# ETH-input.net
KiCad netlist of a schematic drawn in Altium Designer
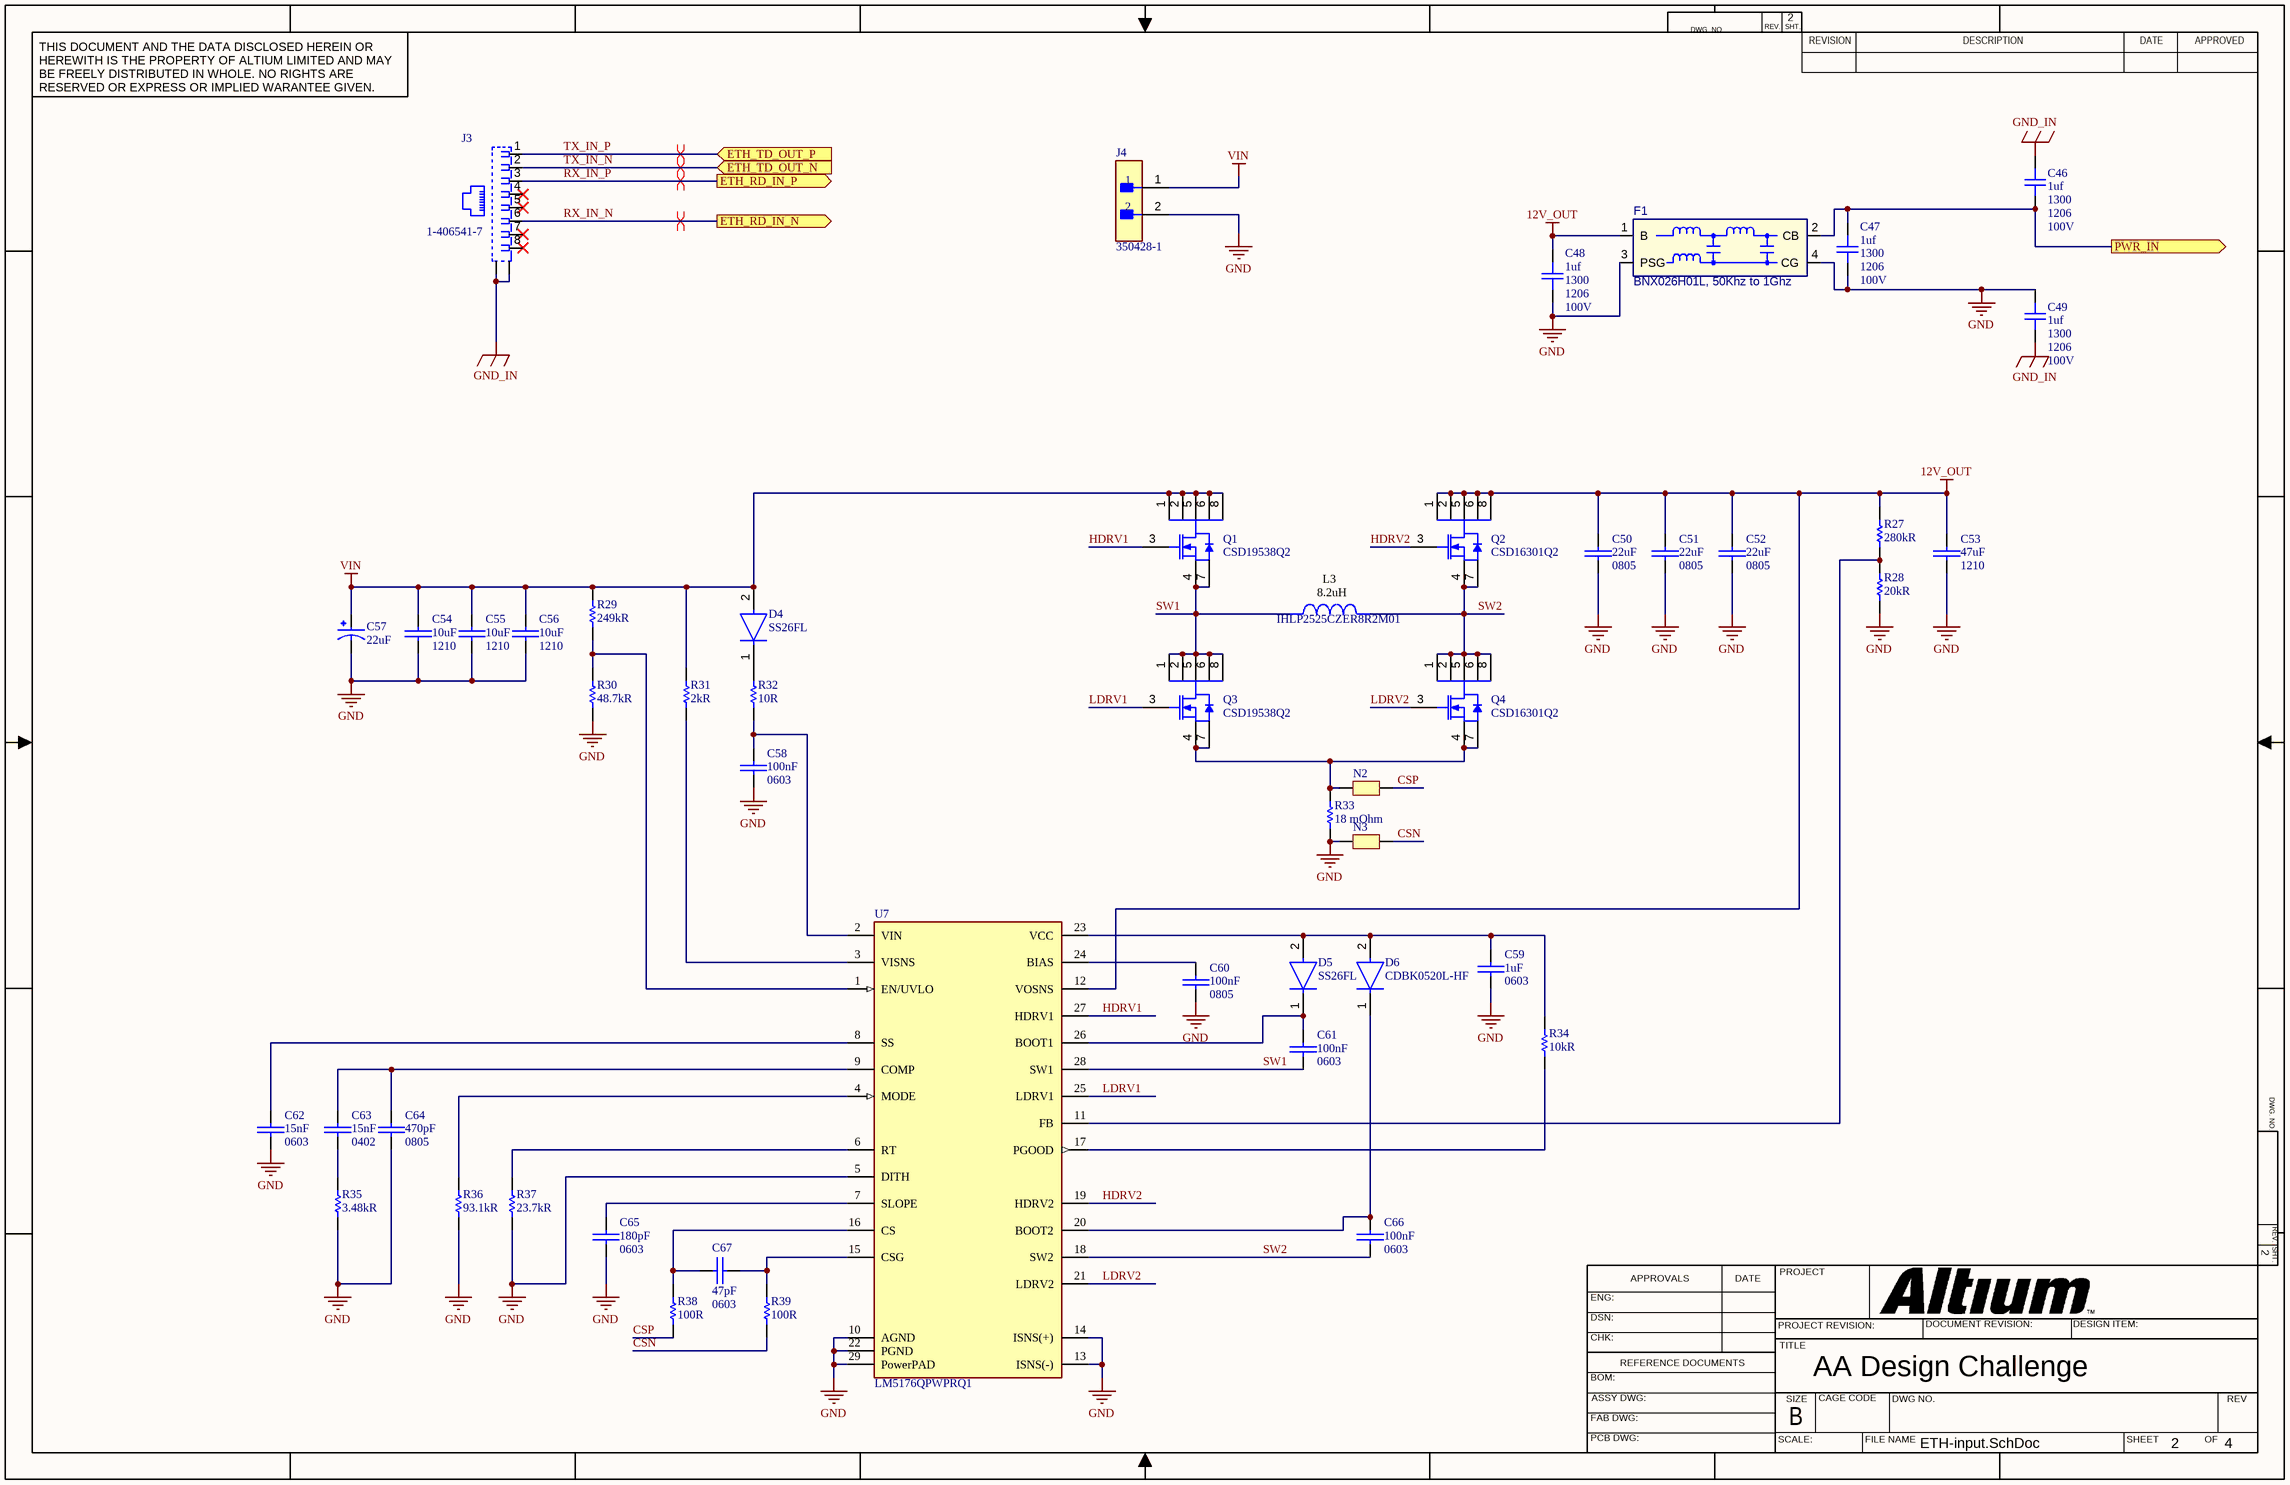
[diagram p0: ETH-input.SchDoc]

(export (version "E")
  (design (tool "Eeschema 10.0.6"))
  (components
    (comp (ref "C46")
      (value "1uf")
      (footprint "CAPC3216_IS1206N_3D")
      (description "Capacitor - 1uf 100V 10% X7R 1206")
      (fields
        (field (name "PACSTAR PN") "1300")
        (field (name "TOLERANCE") "+/-10%")
        (field (name "MANUFACTURER") "Samsung Electro-Mechanics")
        (field (name "CASE-EIA") "1206")
        (field (name "RATED VOLTAGE") "100V")
        (field (name "CHECKED BY") "xxx")
      )
      (libsource (lib "AA-Design-Challenge") (part "1300"))
    )
    (comp (ref "C47")
      (value "1uf")
      (footprint "CAPC3216_IS1206N_3D")
      (description "Capacitor - 1uf 100V 10% X7R 1206")
      (fields
        (field (name "PACSTAR PN") "1300")
        (field (name "TOLERANCE") "+/-10%")
        (field (name "MANUFACTURER") "Samsung Electro-Mechanics")
        (field (name "CASE-EIA") "1206")
        (field (name "RATED VOLTAGE") "100V")
        (field (name "CHECKED BY") "xxx")
      )
      (libsource (lib "AA-Design-Challenge") (part "1300"))
    )
    (comp (ref "C48")
      (value "1uf")
      (footprint "CAPC3216_IS1206N_3D")
      (description "Capacitor - 1uf 100V 10% X7R 1206")
      (fields
        (field (name "PACSTAR PN") "1300")
        (field (name "TOLERANCE") "+/-10%")
        (field (name "MANUFACTURER") "Samsung Electro-Mechanics")
        (field (name "CASE-EIA") "1206")
        (field (name "RATED VOLTAGE") "100V")
        (field (name "CHECKED BY") "xxx")
      )
      (libsource (lib "AA-Design-Challenge") (part "1300"))
    )
    (comp (ref "C49")
      (value "1uf")
      (footprint "CAPC3216_IS1206N_3D")
      (description "Capacitor - 1uf 100V 10% X7R 1206")
      (fields
        (field (name "PACSTAR PN") "1300")
        (field (name "TOLERANCE") "+/-10%")
        (field (name "MANUFACTURER") "Samsung Electro-Mechanics")
        (field (name "CASE-EIA") "1206")
        (field (name "RATED VOLTAGE") "100V")
        (field (name "CHECKED BY") "xxx")
      )
      (libsource (lib "AA-Design-Challenge") (part "1300"))
    )
    (comp (ref "C50")
      (value "22uF")
      (footprint "CAPC2012X145USR")
      (description "C Series 0805 22 uF 35 V ±20 % Tolerance X5R SMT Multilayer Ceramic Capacitor")
      (fields
        (field (name "MANUFACTURER") "TDK")
        (field (name "MANUFACTURER PART NUMBER") "C2012X5R1V226M125AC")
        (field (name "CASE/PACKAGE") "0805")
      )
      (libsource (lib "AA-Design-Challenge") (part "CAP CER 10UF 63V X7R 1210"))
    )
    (comp (ref "C51")
      (value "22uF")
      (footprint "CAPC2012X145USR")
      (description "C Series 0805 22 uF 35 V ±20 % Tolerance X5R SMT Multilayer Ceramic Capacitor")
      (fields
        (field (name "MANUFACTURER") "TDK")
        (field (name "MANUFACTURER PART NUMBER") "C2012X5R1V226M125AC")
        (field (name "CASE/PACKAGE") "0805")
      )
      (libsource (lib "AA-Design-Challenge") (part "CAP CER 10UF 63V X7R 1210"))
    )
    (comp (ref "C52")
      (value "22uF")
      (footprint "CAPC2012X145USR")
      (description "C Series 0805 22 uF 35 V ±20 % Tolerance X5R SMT Multilayer Ceramic Capacitor")
      (fields
        (field (name "MANUFACTURER") "TDK")
        (field (name "MANUFACTURER PART NUMBER") "C2012X5R1V226M125AC")
        (field (name "CASE/PACKAGE") "0805")
      )
      (libsource (lib "AA-Design-Challenge") (part "CAP CER 10UF 63V X7R 1210"))
    )
    (comp (ref "C53")
      (value "47uF")
      (footprint "C1210")
      (description "1210 47 uF 16 V ±10% Tolerance X5R SMT Multilayer Ceramic Capacitor")
      (fields
        (field (name "MANUFACTURER") "Samsung Electro-Mechanics")
        (field (name "MANUFACTURER PART NUMBER") "CL32A476KOJNNNE")
        (field (name "CASE/PACKAGE") "1210")
      )
      (libsource (lib "AA-Design-Challenge") (part "CAP CER 10UF 63V X7R 1210"))
    )
    (comp (ref "C54")
      (value "10uF")
      (footprint "AA-Design-Challenge:C1210")
      (description "Multilayer Ceramic Capacitors MLCC - SMD/SMT 1210 10uF 63volts *Derate Voltage/Temp")
      (fields
        (field (name "MANUFACTURER") "Samsung Electro-Mechanics")
        (field (name "MANUFACTURER PART NUMBER") "CL32B106KMVNNWE")
        (field (name "CASE/PACKAGE") "1210")
      )
      (libsource (lib "AA-Design-Challenge") (part "CAP CER 10UF 63V X7R 1210"))
    )
    (comp (ref "C55")
      (value "10uF")
      (footprint "AA-Design-Challenge:C1210")
      (description "Multilayer Ceramic Capacitors MLCC - SMD/SMT 1210 10uF 63volts *Derate Voltage/Temp")
      (fields
        (field (name "MANUFACTURER") "Samsung Electro-Mechanics")
        (field (name "MANUFACTURER PART NUMBER") "CL32B106KMVNNWE")
        (field (name "CASE/PACKAGE") "1210")
      )
      (libsource (lib "AA-Design-Challenge") (part "CAP CER 10UF 63V X7R 1210"))
    )
    (comp (ref "C56")
      (value "10uF")
      (footprint "AA-Design-Challenge:C1210")
      (description "Multilayer Ceramic Capacitors MLCC - SMD/SMT 1210 10uF 63volts *Derate Voltage/Temp")
      (fields
        (field (name "MANUFACTURER") "Samsung Electro-Mechanics")
        (field (name "MANUFACTURER PART NUMBER") "CL32B106KMVNNWE")
        (field (name "CASE/PACKAGE") "1210")
      )
      (libsource (lib "AA-Design-Challenge") (part "CAP CER 10UF 63V X7R 1210"))
    )
    (comp (ref "C57")
      (value "22uF")
      (footprint "CAP_EEEHC1H220XP")
      (description "22ÂµF 50V Aluminum Electrolytic Capacitors Radial, Can - SMD 3000 Hrs @ 105Â°C")
      (fields
        (field (name "MANUFACTURER") "Panasonic")
        (field (name "MANUFACTURER PART NUMBER") "EEEHC1H220XP")
      )
      (libsource (lib "AA-Design-Challenge") (part "EEEHC1H220XP"))
    )
    (comp (ref "C58")
      (value "100nF")
      (footprint "AA-Design-Challenge:CAP_0603")
      (description "CGA Series 0603 100 nF 50 V ±10 % Tolerance X7R SMT Multilayer Ceramic Capacitor")
      (fields
        (field (name "MANUFACTURER") "TDK")
        (field (name "MANUFACTURER PART NUMBER") "CGA3E2X7R1H104K080AA")
        (field (name "CASE/PACKAGE") "0603")
      )
      (libsource (lib "AA-Design-Challenge") (part "CAP CER 10UF 63V X7R 1210"))
    )
    (comp (ref "C59")
      (value "1uF")
      (footprint "AA-Design-Challenge:CAP_0603")
      (description "0603 1 uF 16 V ±10% Tolerance X7R SMT Multilayer Ceramic Capacitor")
      (fields
        (field (name "MANUFACTURER") "Samsung Electro-Mechanics")
        (field (name "MANUFACTURER PART NUMBER") "CL10B105KO8NNNC")
        (field (name "CASE/PACKAGE") "0603")
      )
      (libsource (lib "AA-Design-Challenge") (part "CAP CER 10UF 63V X7R 1210"))
    )
    (comp (ref "C60")
      (value "100nF")
      (footprint "AA-Design-Challenge:CAPC2012X145USR")
      (description "0805 100 nF 25V ±10 % Tolerance X7R Surface Mount Multilayer Ceramic Capacitor")
      (fields
        (field (name "MANUFACTURER") "Kyocera AVX")
        (field (name "MANUFACTURER PART NUMBER") "08053C104KAT2A")
        (field (name "CASE/PACKAGE") "0805")
      )
      (libsource (lib "AA-Design-Challenge") (part "CAP CER 10UF 63V X7R 1210"))
    )
    (comp (ref "C61")
      (value "100nF")
      (footprint "AA-Design-Challenge:CAP_0603")
      (description "Cap Ceramic 0.1uF 25V X7R 10% SMD 0603 125 Paper T/R")
      (fields
        (field (name "MANUFACTURER") "Kyocera AVX")
        (field (name "MANUFACTURER PART NUMBER") "06033C104KAT2A")
        (field (name "CASE/PACKAGE") "0603")
      )
      (libsource (lib "AA-Design-Challenge") (part "CAP CER 10UF 63V X7R 1210"))
    )
    (comp (ref "C62")
      (value "15nF")
      (footprint "AA-Design-Challenge:CAP_0603")
      (description "0603 C 15nF Ceramic Multilayer Capacitor; 25 V; +125degC; C0G Dielectric; +/-5%")
      (fields
        (field (name "MANUFACTURER") "KEMET")
        (field (name "MANUFACTURER PART NUMBER") "C0603C153J3GACTU")
        (field (name "CASE/PACKAGE") "0603")
      )
      (libsource (lib "AA-Design-Challenge") (part "CAP CER 10UF 63V X7R 1210"))
    )
    (comp (ref "C63")
      (value "15nF")
      (footprint "AA-Design-Challenge:CAPC1005X55USR")
      (description "Cap Ceramic 0.015uF 50V X7R 10% SMD 0402 125°C Punched Paper T/R")
      (fields
        (field (name "MANUFACTURER") "TDK")
        (field (name "MANUFACTURER PART NUMBER") "CGA2B3X7R1H153K050BB")
        (field (name "CASE/PACKAGE") "0402")
      )
      (libsource (lib "AA-Design-Challenge") (part "CAP CER 10UF 63V X7R 1210"))
    )
    (comp (ref "C64")
      (value "470pF")
      (footprint "AA-Design-Challenge:CAPC2012X145USR")
      (description "CAP CER 470PF 50V C0G/NP0 0805")
      (fields
        (field (name "MANUFACTURER") "Wurth Elektronik")
        (field (name "MANUFACTURER PART NUMBER") "885012007061")
        (field (name "CASE/PACKAGE") "0805")
      )
      (libsource (lib "AA-Design-Challenge") (part "CAP CER 10UF 63V X7R 1210"))
    )
    (comp (ref "C65")
      (value "180pF")
      (footprint "AA-Design-Challenge:CAP_0603")
      (description "Surface Mount Ceramic Multilayer Capacitor 180pF 5% C0G 50V 0603 Paper T/R")
      (fields
        (field (name "MANUFACTURER") "Yageo")
        (field (name "MANUFACTURER PART NUMBER") "CC0603JRNPO9BN181")
        (field (name "CASE/PACKAGE") "0603")
      )
      (libsource (lib "AA-Design-Challenge") (part "CAP CER 10UF 63V X7R 1210"))
    )
    (comp (ref "C66")
      (value "100nF")
      (footprint "AA-Design-Challenge:CAP_0603")
      (description "Cap Ceramic 0.1uF 25V X7R 10% SMD 0603 125 Paper T/R")
      (fields
        (field (name "MANUFACTURER") "Kyocera AVX")
        (field (name "MANUFACTURER PART NUMBER") "06033C104KAT2A")
        (field (name "CASE/PACKAGE") "0603")
      )
      (libsource (lib "AA-Design-Challenge") (part "CAP CER 10UF 63V X7R 1210"))
    )
    (comp (ref "C67")
      (value "47pF")
      (footprint "AA-Design-Challenge:CAP_0603")
      (description "0603 47 pF 50 V ±5% Tolerance C0G/NP0 Surface Mount Multilayer Ceramic Capacitor")
      (fields
        (field (name "MANUFACTURER") "Kyocera AVX")
        (field (name "MANUFACTURER PART NUMBER") "06035A470JAT2A")
        (field (name "CASE/PACKAGE") "0603")
      )
      (libsource (lib "AA-Design-Challenge") (part "CAP CER 10UF 63V X7R 1210"))
    )
    (comp (ref "D4")
      (value "SS26FL")
      (footprint "SOD-123F")
      (description "DIODE SCHOTTKY 60V 2A SOD123F")
      (fields (field (name "MANUFACTURER") "ON Semiconductor / Fairchild"))
      (libsource (lib "AA-Design-Challenge") (part "d7152d700b627762746794eb795d46e"))
    )
    (comp (ref "D5")
      (value "SS26FL")
      (footprint "SOD-123F")
      (description "DIODE SCHOTTKY 60V 2A SOD123F")
      (fields (field (name "MANUFACTURER") "ON Semiconductor / Fairchild"))
      (libsource (lib "AA-Design-Challenge") (part "d7152d700b627762746794eb795d46e"))
    )
    (comp (ref "D6")
      (value "CDBK0520L-HF")
      (footprint "AA-Design-Challenge:SOD-123F _CDBK")
      (description "DIODE SCHOTTKY 20V 500MA SOD123F")
      (fields
        (field (name "MANUFACTURER") "Nexperia")
        (field (name "MANUFACTURER PART NUMBER") "PMEG2005EH,115")
      )
      (libsource (lib "AA-Design-Challenge") (part "d7152d700b627762746794eb795d46e"))
    )
    (comp (ref "F1")
      (value "BNX026H01L, 50Khz to 1Ghz")
      (footprint "1359")
      (description "IC - FILTER, EMI 15A 50V 50KHZ-1GHZ SMD")
      (fields (field (name "MFG") "MURATA") (field (name "MANUFACTURER") "Murata"))
      (libsource (lib "AA-Design-Challenge") (part "1359"))
    )
    (comp (ref "J3")
      (value "1-406541-7")
      (footprint "TE_1-406507-5")
      (description "Conn RJ-45 F 8 POS 1.02mm Solder RA Thru-Hole 10 Terminal 1 Port Cat 5 Box/Tray")
      (fields (field (name "MANUFACTURER") "TE Connectivity"))
      (libsource (lib "AA-Design-Challenge") (part "1-406541-7"))
    )
    (comp (ref "J4")
      (value "350428-1")
      (footprint "FP-350428-1-MFG")
      (description "CONN HEADER VERT 2POS 6.35MM")
      (fields
        (field (name "OCTOPART") "https://octopart.com/350428-1-te+connectivity-46505355")
        (field (name "MANUFACTURER") "TE Connectivity")
      )
      (libsource (lib "AA-Design-Challenge") (part "3bc925449376181038e59eaffc5286c"))
    )
    (comp (ref "L3")
      (value "8.2uH")
      (footprint "INDM686X647X300N")
      (description "FIXED IND 8.2UH 4A 68 MOHM SMD")
      (fields
        (field (name "MANUFACTURER") "Vishay Dale")
        (field (name "MANUFACTURER PART NUMBER") "IHLP2525CZER8R2M01")
        (field (name "TOLERANCE") "20%")
      )
      (libsource (lib "AA-Design-Challenge") (part "L1"))
    )
    (comp (ref "N2")
      (value "NT")
      (footprint "Net Tie 10mil")
      (libsource (lib "OP_Library") (part "Net Tie 10mil"))
    )
    (comp (ref "N3")
      (value "NT")
      (footprint "Net Tie 10mil")
      (libsource (lib "OP_Library") (part "Net Tie 10mil"))
    )
    (comp (ref "Q1")
      (value "CSD19538Q2")
      (footprint "TRANS_6WSON_2X2")
      (description "100-V, N channel NexFET™ power MOSFET, single SON 2 mm x 2 mm, 59 mOhm 6-WSON -55 to 150")
      (fields
        (field (name "MANUFACTURER") "Texas Instruments")
        (field (name "MANUFACTURER PART NUMBER") "CSD19538Q2T")
      )
      (libsource (lib "AA-Design-Challenge") (part "CSD19538Q2"))
    )
    (comp (ref "Q2")
      (value "CSD16301Q2")
      (footprint "TRANS_6WSON_2X2")
      (description "MOSFET N-CH 25V 6-SON")
      (fields (field (name "MANUFACTURER") "Texas Instruments"))
      (libsource (lib "AA-Design-Challenge") (part "CSD16301Q2"))
    )
    (comp (ref "Q3")
      (value "CSD19538Q2")
      (footprint "TRANS_6WSON_2X2")
      (description "100-V, N channel NexFET™ power MOSFET, single SON 2 mm x 2 mm, 59 mOhm 6-WSON -55 to 150")
      (fields
        (field (name "MANUFACTURER") "Texas Instruments")
        (field (name "MANUFACTURER PART NUMBER") "CSD19538Q2T")
      )
      (libsource (lib "AA-Design-Challenge") (part "CSD19538Q2"))
    )
    (comp (ref "Q4")
      (value "CSD16301Q2")
      (footprint "TRANS_6WSON_2X2")
      (description "MOSFET N-CH 25V 6-SON")
      (fields (field (name "MANUFACTURER") "Texas Instruments"))
      (libsource (lib "AA-Design-Challenge") (part "CSD16301Q2"))
    )
    (comp (ref "R27")
      (value "280kR")
      (footprint "R0603")
      (description "Res Thick Film 0603 280K Ohm 1% 1/10W ±100ppm/°C Molded SMD SMD Paper T/R")
      (fields
        (field (name "MANUFACTURER") "Vishay")
        (field (name "MANUFACTURER PART NUMBER") "CRCW0603280KFKEA")
      )
      (libsource (lib "AA-Design-Challenge") (part "RES SMD 2K OHM 1% 1/10W 0603"))
    )
    (comp (ref "R28")
      (value "20kR")
      (footprint "R0603")
      (description "Res General Purpose Thick Film 0603 20K Ohm 1% 1/10W ±100ppm/°C Molded SMD Paper T/R")
      (fields
        (field (name "MANUFACTURER") "Yageo")
        (field (name "MANUFACTURER PART NUMBER") "RC0603FR-0720KL")
      )
      (libsource (lib "AA-Design-Challenge") (part "RES SMD 2K OHM 1% 1/10W 0603"))
    )
    (comp (ref "R29")
      (value "249kR")
      (footprint "RESC0603X26N")
      (description "Res Thick Film 0201 249K Ohm 1% 1/20W ±200ppm/°C Molded SMD Paper T/R")
      (fields
        (field (name "MANUFACTURER") "Yageo")
        (field (name "MANUFACTURER PART NUMBER") "RC0201FR-07249KL")
      )
      (libsource (lib "AA-Design-Challenge") (part "RES 249K OHM 1% 1/20W 0201"))
    )
    (comp (ref "R30")
      (value "48.7kR")
      (footprint "RESC1005X40USR")
      (description "Res Thick Film 0402 48.7K Ohm 1% 1/16W ±100ppm/°C Molded SMD SMD Paper T/R")
      (fields
        (field (name "MANUFACTURER") "Vishay")
        (field (name "MANUFACTURER PART NUMBER") "CRCW040248K7FKED")
      )
      (libsource (lib "AA-Design-Challenge") (part "RES SMD 48.7K OHM 1% 1/16W 0402"))
    )
    (comp (ref "R31")
      (value "2kR")
      (footprint "R0603")
      (description "Res Thick Film 0603 2K Ohm 1% 1/10W ±100ppm/°C Molded SMD Paper T/R")
      (fields
        (field (name "MANUFACTURER") "Vishay")
        (field (name "MANUFACTURER PART NUMBER") "CRCW06032K00FKEB")
      )
      (libsource (lib "AA-Design-Challenge") (part "RES SMD 2K OHM 1% 1/10W 0603"))
    )
    (comp (ref "R32")
      (value "10R")
      (footprint "R0603")
      (description "Res Thick Film 0603 10 Ohm 1% 1/10W ±200ppm/°C Molded SMD Paper T/R")
      (fields
        (field (name "MANUFACTURER") "Yageo")
        (field (name "MANUFACTURER PART NUMBER") "RC0603FR-0710RL")
      )
      (libsource (lib "AA-Design-Challenge") (part "RES SMD 2K OHM 1% 1/10W 0603"))
    )
    (comp (ref "R33")
      (value "18 mOhm")
      (footprint "RES 1206N - 71")
      (description "Res Thick Film 1206 0.018 Ohm 1% 1W ±75ppm/C Pad SMD Automotive T/R")
      (fields
        (field (name "MANUFACTURER") "Panasonic")
        (field (name "MANUFACTURER PART NUMBER") "ERJ8CWFR018V")
      )
      (libsource (lib "AA-Design-Challenge") (part "ERJ8CWFR018V"))
    )
    (comp (ref "R34")
      (value "10kR")
      (footprint "R0603")
      (description "RES SMD 10K OHM 1% 1/10W 0603")
      (fields
        (field (name "MANUFACTURER") "Yageo")
        (field (name "MANUFACTURER PART NUMBER") "RC0603FR-0710KL")
      )
      (libsource (lib "AA-Design-Challenge") (part "RES SMD 2K OHM 1% 1/10W 0603"))
    )
    (comp (ref "R35")
      (value "3.48kR")
      (footprint "AA-Design-Challenge:RESC1005X40USR")
      (description "Res Thick Film 0402 3.48K Ohm 1% 1/16W ±100ppm/°C Molded SMD Paper T/R")
      (fields
        (field (name "MANUFACTURER") "Vishay")
        (field (name "MANUFACTURER PART NUMBER") "CRCW04023K48FKED")
      )
      (libsource (lib "AA-Design-Challenge") (part "RES SMD 2K OHM 1% 1/10W 0603"))
    )
    (comp (ref "R36")
      (value "93.1kR")
      (footprint "AA-Design-Challenge:R0603")
      (description "Res Thick Film 0603 93.1K Ohm 1% 1/10W ±100ppm/°C Molded SMD SMD Paper T/R")
      (fields
        (field (name "MANUFACTURER") "Yageo")
        (field (name "MANUFACTURER PART NUMBER") "RC0603FR-0793K1L")
      )
      (libsource (lib "AA-Design-Challenge") (part "RES SMD 2K OHM 1% 1/10W 0603"))
    )
    (comp (ref "R37")
      (value "23.7kR")
      (footprint "RESC0603X26N")
      (description "Res General Purpose Thick Film 0201 23.7k Ohm 1% 1/20W ±200ppm/°C Molded SMD Paper T/R")
      (fields
        (field (name "MANUFACTURER") "Yageo")
        (field (name "MANUFACTURER PART NUMBER") "RC0201FR-0723K7L")
      )
      (libsource (lib "AA-Design-Challenge") (part "RES SMD 2K OHM 1% 1/10W 0603"))
    )
    (comp (ref "R38")
      (value "100R")
      (footprint "AA-Design-Challenge:R0603")
      (description "Res Thick Film 0603 100 Ohm 1% 1/10W ±100ppm/°C Molded SMD Paper T/R")
      (fields
        (field (name "MANUFACTURER") "Vishay Dale")
        (field (name "MANUFACTURER PART NUMBER") "CRCW0603100RFKEA")
      )
      (libsource (lib "AA-Design-Challenge") (part "RES SMD 2K OHM 1% 1/10W 0603"))
    )
    (comp (ref "R39")
      (value "100R")
      (footprint "R0603")
      (description "Res Thick Film 0603 100 Ohm 1% 1/10W ±100ppm/°C Molded SMD Paper T/R")
      (fields
        (field (name "MANUFACTURER") "Vishay Dale")
        (field (name "MANUFACTURER PART NUMBER") "CRCW0603100RFKEA")
      )
      (libsource (lib "AA-Design-Challenge") (part "RES SMD 2K OHM 1% 1/10W 0603"))
    )
    (comp (ref "U7")
      (value "LM5176QPWPRQ1")
      (footprint "IC_LM5176QPWPRQ1")
      (description "55-V wide VIN synchronous 4-switch buck-boost controller, AEC-Q100 qualified 28-HTSSOP -40 to 125")
      (fields (field (name "MANUFACTURER") "Texas Instruments"))
      (libsource (lib "AA-Design-Challenge") (part "LM5176QPWPRQ1"))
    )
  )
  (nets
    (net (code "1") (name "/CSN") (class "Default")
      (node (ref "N3") (pin "2") (pinfunction "2_2") (pintype "passive"))
      (node (ref "R39") (pin "1") (pinfunction "1_1") (pintype "passive"))
    )
    (net (code "2") (name "/CSP") (class "Default")
      (node (ref "N2") (pin "2") (pinfunction "2_2") (pintype "passive"))
      (node (ref "R38") (pin "1") (pinfunction "1_1") (pintype "passive"))
    )
    (net (code "3") (name "/HDRV1") (class "Default")
      (node (ref "Q1") (pin "3") (pinfunction "GATE_3") (pintype "passive"))
      (node (ref "U7") (pin "27") (pinfunction "HDRV1_27") (pintype "power_in"))
    )
    (net (code "4") (name "/HDRV2") (class "Default")
      (node (ref "Q2") (pin "3") (pinfunction "GATE_3") (pintype "passive"))
      (node (ref "U7") (pin "19") (pinfunction "HDRV2_19") (pintype "power_in"))
    )
    (net (code "5") (name "/LDRV1") (class "Default")
      (node (ref "Q3") (pin "3") (pinfunction "GATE_3") (pintype "passive"))
      (node (ref "U7") (pin "25") (pinfunction "LDRV1_25") (pintype "power_in"))
    )
    (net (code "6") (name "/LDRV2") (class "Default")
      (node (ref "Q4") (pin "3") (pinfunction "GATE_3") (pintype "passive"))
      (node (ref "U7") (pin "21") (pinfunction "LDRV2_21") (pintype "power_in"))
    )
    (net (code "7") (name "/PWR_IN") (class "Default")
      (node (ref "C46") (pin "2") (pinfunction "2_2") (pintype "passive"))
      (node (ref "C47") (pin "1") (pinfunction "1_1") (pintype "passive"))
      (node (ref "F1") (pin "2") (pinfunction "CB_2") (pintype "passive"))
    )
    (net (code "8") (name "/RX_IN_N") (class "Default")
      (node (ref "J3") (pin "6") (pinfunction "6_6") (pintype "passive"))
    )
    (net (code "9") (name "/RX_IN_P") (class "Default")
      (node (ref "J3") (pin "3") (pinfunction "3_3") (pintype "passive"))
    )
    (net (code "10") (name "/SW1") (class "Default")
      (node (ref "C61") (pin "2") (pinfunction "2_2") (pintype "passive"))
      (node (ref "L3") (pin "1") (pinfunction "1_1") (pintype "passive"))
      (node (ref "Q1") (pin "4") (pinfunction "SOURCE_4") (pintype "passive"))
      (node (ref "Q1") (pin "7") (pinfunction "SOURCE_7") (pintype "passive"))
      (node (ref "Q3") (pin "1") (pinfunction "DRAIN_1") (pintype "passive"))
      (node (ref "Q3") (pin "2") (pinfunction "DRAIN_2") (pintype "passive"))
      (node (ref "Q3") (pin "5") (pinfunction "DRAIN_5") (pintype "passive"))
      (node (ref "Q3") (pin "6") (pinfunction "DRAIN_6") (pintype "passive"))
      (node (ref "Q3") (pin "8") (pinfunction "DRAIN_8") (pintype "passive"))
      (node (ref "U7") (pin "28") (pinfunction "SW1_28") (pintype "power_in"))
    )
    (net (code "11") (name "/SW2") (class "Default")
      (node (ref "C66") (pin "2") (pinfunction "2_2") (pintype "passive"))
      (node (ref "L3") (pin "2") (pinfunction "2_2") (pintype "passive"))
      (node (ref "Q2") (pin "4") (pinfunction "SOURCE_4") (pintype "passive"))
      (node (ref "Q2") (pin "7") (pinfunction "SOURCE_7") (pintype "passive"))
      (node (ref "Q4") (pin "1") (pinfunction "DRAIN_1") (pintype "passive"))
      (node (ref "Q4") (pin "2") (pinfunction "DRAIN_2") (pintype "passive"))
      (node (ref "Q4") (pin "5") (pinfunction "DRAIN_5") (pintype "passive"))
      (node (ref "Q4") (pin "6") (pinfunction "DRAIN_6") (pintype "passive"))
      (node (ref "Q4") (pin "8") (pinfunction "DRAIN_8") (pintype "passive"))
      (node (ref "U7") (pin "18") (pinfunction "SW2_18") (pintype "power_in"))
    )
    (net (code "12") (name "/TX_IN_N") (class "Default")
      (node (ref "J3") (pin "2") (pinfunction "2_2") (pintype "passive"))
    )
    (net (code "13") (name "/TX_IN_P") (class "Default")
      (node (ref "J3") (pin "1") (pinfunction "1_1") (pintype "passive"))
    )
    (net (code "14") (name "12V_OUT") (class "Default")
      (node (ref "C48") (pin "1") (pinfunction "1_1") (pintype "passive"))
      (node (ref "C50") (pin "1") (pinfunction "1_1") (pintype "passive"))
      (node (ref "C51") (pin "1") (pinfunction "1_1") (pintype "passive"))
      (node (ref "C52") (pin "1") (pinfunction "1_1") (pintype "passive"))
      (node (ref "C53") (pin "1") (pinfunction "1_1") (pintype "passive"))
      (node (ref "F1") (pin "1") (pinfunction "B_1") (pintype "passive"))
      (node (ref "Q2") (pin "1") (pinfunction "DRAIN_1") (pintype "passive"))
      (node (ref "Q2") (pin "2") (pinfunction "DRAIN_2") (pintype "passive"))
      (node (ref "Q2") (pin "5") (pinfunction "DRAIN_5") (pintype "passive"))
      (node (ref "Q2") (pin "6") (pinfunction "DRAIN_6") (pintype "passive"))
      (node (ref "Q2") (pin "8") (pinfunction "DRAIN_8") (pintype "passive"))
      (node (ref "R27") (pin "2") (pinfunction "2_2") (pintype "passive"))
      (node (ref "U7") (pin "12") (pinfunction "VOSNS_12") (pintype "passive"))
    )
    (net (code "15") (name "GND") (class "Default")
      (node (ref "C47") (pin "2") (pinfunction "2_2") (pintype "passive"))
      (node (ref "C48") (pin "2") (pinfunction "2_2") (pintype "passive"))
      (node (ref "C49") (pin "2") (pinfunction "2_2") (pintype "passive"))
      (node (ref "C50") (pin "2") (pinfunction "2_2") (pintype "passive"))
      (node (ref "C51") (pin "2") (pinfunction "2_2") (pintype "passive"))
      (node (ref "C52") (pin "2") (pinfunction "2_2") (pintype "passive"))
      (node (ref "C53") (pin "2") (pinfunction "2_2") (pintype "passive"))
      (node (ref "C54") (pin "2") (pinfunction "2_2") (pintype "passive"))
      (node (ref "C55") (pin "2") (pinfunction "2_2") (pintype "passive"))
      (node (ref "C56") (pin "2") (pinfunction "2_2") (pintype "passive"))
      (node (ref "C57") (pin "2") (pinfunction "2_2") (pintype "passive"))
      (node (ref "C58") (pin "2") (pinfunction "2_2") (pintype "passive"))
      (node (ref "C59") (pin "2") (pinfunction "2_2") (pintype "passive"))
      (node (ref "C60") (pin "2") (pinfunction "2_2") (pintype "passive"))
      (node (ref "C62") (pin "2") (pinfunction "2_2") (pintype "passive"))
      (node (ref "C64") (pin "2") (pinfunction "2_2") (pintype "passive"))
      (node (ref "C65") (pin "2") (pinfunction "2_2") (pintype "passive"))
      (node (ref "F1") (pin "3") (pinfunction "PSG_3") (pintype "passive"))
      (node (ref "F1") (pin "4") (pinfunction "CG_4") (pintype "passive"))
      (node (ref "J4") (pin "2") (pinfunction "2_2") (pintype "passive"))
      (node (ref "N3") (pin "1") (pinfunction "1_1") (pintype "passive"))
      (node (ref "R28") (pin "1") (pinfunction "1_1") (pintype "passive"))
      (node (ref "R30") (pin "1") (pinfunction "1_1") (pintype "passive"))
      (node (ref "R33") (pin "1") (pinfunction "1_1") (pintype "passive"))
      (node (ref "R35") (pin "1") (pinfunction "1_1") (pintype "passive"))
      (node (ref "R36") (pin "1") (pinfunction "1_1") (pintype "passive"))
      (node (ref "R37") (pin "1") (pinfunction "1_1") (pintype "passive"))
      (node (ref "U7") (pin "10") (pinfunction "AGND_10") (pintype "power_in"))
      (node (ref "U7") (pin "13") (pinfunction "ISNS(-)_13") (pintype "passive"))
      (node (ref "U7") (pin "14") (pinfunction "ISNS(+)_14") (pintype "passive"))
      (node (ref "U7") (pin "22") (pinfunction "PGND_22") (pintype "power_in"))
      (node (ref "U7") (pin "29") (pinfunction "PowerPAD_29") (pintype "power_in"))
      (node (ref "U7") (pin "5") (pinfunction "DITH_5") (pintype "passive"))
    )
    (net (code "16") (name "GND_IN") (class "Default")
      (node (ref "C46") (pin "1") (pinfunction "1_1") (pintype "passive"))
      (node (ref "C49") (pin "1") (pinfunction "1_1") (pintype "passive"))
      (node (ref "J3") (pin "10") (pinfunction "S2_10") (pintype "passive"))
      (node (ref "J3") (pin "9") (pinfunction "S1_9") (pintype "passive"))
    )
    (net (code "17") (name "Net-(C63-Pad2)") (class "Default")
      (node (ref "C63") (pin "2") (pinfunction "2_2") (pintype "passive"))
      (node (ref "R35") (pin "2") (pinfunction "2_2") (pintype "passive"))
    )
    (net (code "18") (name "Net-(D4-C)") (class "Default")
      (node (ref "D4") (pin "1") (pinfunction "C_1") (pintype "passive"))
      (node (ref "R32") (pin "2") (pinfunction "2_2") (pintype "passive"))
    )
    (net (code "19") (name "Net-(D5-A)") (class "Default")
      (node (ref "C59") (pin "1") (pinfunction "1_1") (pintype "passive"))
      (node (ref "D5") (pin "2") (pinfunction "A_2") (pintype "passive"))
      (node (ref "D6") (pin "2") (pinfunction "A_2") (pintype "passive"))
      (node (ref "R34") (pin "2") (pinfunction "2_2") (pintype "passive"))
      (node (ref "U7") (pin "23") (pinfunction "VCC_23") (pintype "power_in"))
    )
    (net (code "20") (name "Net-(D5-C)") (class "Default")
      (node (ref "C61") (pin "1") (pinfunction "1_1") (pintype "passive"))
      (node (ref "D5") (pin "1") (pinfunction "C_1") (pintype "passive"))
      (node (ref "U7") (pin "26") (pinfunction "BOOT1_26") (pintype "power_in"))
    )
    (net (code "21") (name "Net-(D6-C)") (class "Default")
      (node (ref "C66") (pin "1") (pinfunction "1_1") (pintype "passive"))
      (node (ref "D6") (pin "1") (pinfunction "C_1") (pintype "passive"))
      (node (ref "U7") (pin "20") (pinfunction "BOOT2_20") (pintype "power_in"))
    )
    (net (code "22") (name "Net-(N2-Pad1)") (class "Default")
      (node (ref "N2") (pin "1") (pinfunction "1_1") (pintype "passive"))
      (node (ref "Q3") (pin "4") (pinfunction "SOURCE_4") (pintype "passive"))
      (node (ref "Q3") (pin "7") (pinfunction "SOURCE_7") (pintype "passive"))
      (node (ref "Q4") (pin "4") (pinfunction "SOURCE_4") (pintype "passive"))
      (node (ref "Q4") (pin "7") (pinfunction "SOURCE_7") (pintype "passive"))
      (node (ref "R33") (pin "2") (pinfunction "2_2") (pintype "passive"))
    )
    (net (code "23") (name "Net-(U7-BIAS)") (class "Default")
      (node (ref "C60") (pin "1") (pinfunction "1_1") (pintype "passive"))
      (node (ref "U7") (pin "24") (pinfunction "BIAS_24") (pintype "passive"))
    )
    (net (code "24") (name "Net-(U7-COMP)") (class "Default")
      (node (ref "C63") (pin "1") (pinfunction "1_1") (pintype "passive"))
      (node (ref "C64") (pin "1") (pinfunction "1_1") (pintype "passive"))
      (node (ref "U7") (pin "9") (pinfunction "COMP_9") (pintype "passive"))
    )
    (net (code "25") (name "Net-(U7-CS)") (class "Default")
      (node (ref "C67") (pin "1") (pinfunction "1_1") (pintype "passive"))
      (node (ref "R38") (pin "2") (pinfunction "2_2") (pintype "passive"))
      (node (ref "U7") (pin "16") (pinfunction "CS_16") (pintype "passive"))
    )
    (net (code "26") (name "Net-(U7-CSG)") (class "Default")
      (node (ref "C67") (pin "2") (pinfunction "2_2") (pintype "passive"))
      (node (ref "R39") (pin "2") (pinfunction "2_2") (pintype "passive"))
      (node (ref "U7") (pin "15") (pinfunction "CSG_15") (pintype "passive"))
    )
    (net (code "27") (name "Net-(U7-EN{slash}UVLO)") (class "Default")
      (node (ref "R29") (pin "1") (pinfunction "1_1") (pintype "passive"))
      (node (ref "R30") (pin "2") (pinfunction "2_2") (pintype "passive"))
      (node (ref "U7") (pin "1") (pinfunction "EN/UVLO_1") (pintype "input"))
    )
    (net (code "28") (name "Net-(U7-FB)") (class "Default")
      (node (ref "R27") (pin "1") (pinfunction "1_1") (pintype "passive"))
      (node (ref "R28") (pin "2") (pinfunction "2_2") (pintype "passive"))
      (node (ref "U7") (pin "11") (pinfunction "FB_11") (pintype "passive"))
    )
    (net (code "29") (name "Net-(U7-MODE)") (class "Default")
      (node (ref "R36") (pin "2") (pinfunction "2_2") (pintype "passive"))
      (node (ref "U7") (pin "4") (pinfunction "MODE_4") (pintype "input"))
    )
    (net (code "30") (name "Net-(U7-PGOOD)") (class "Default")
      (node (ref "R34") (pin "1") (pinfunction "1_1") (pintype "passive"))
      (node (ref "U7") (pin "17") (pinfunction "PGOOD_17") (pintype "output"))
    )
    (net (code "31") (name "Net-(U7-RT)") (class "Default")
      (node (ref "R37") (pin "2") (pinfunction "2_2") (pintype "passive"))
      (node (ref "U7") (pin "6") (pinfunction "RT_6") (pintype "passive"))
    )
    (net (code "32") (name "Net-(U7-SLOPE)") (class "Default")
      (node (ref "C65") (pin "1") (pinfunction "1_1") (pintype "passive"))
      (node (ref "U7") (pin "7") (pinfunction "SLOPE_7") (pintype "passive"))
    )
    (net (code "33") (name "Net-(U7-SS)") (class "Default")
      (node (ref "C62") (pin "1") (pinfunction "1_1") (pintype "passive"))
      (node (ref "U7") (pin "8") (pinfunction "SS_8") (pintype "passive"))
    )
    (net (code "34") (name "Net-(U7-VIN)") (class "Default")
      (node (ref "C58") (pin "1") (pinfunction "1_1") (pintype "passive"))
      (node (ref "R32") (pin "1") (pinfunction "1_1") (pintype "passive"))
      (node (ref "U7") (pin "2") (pinfunction "VIN_2") (pintype "power_in"))
    )
    (net (code "35") (name "Net-(U7-VISNS)") (class "Default")
      (node (ref "R31") (pin "1") (pinfunction "1_1") (pintype "passive"))
      (node (ref "U7") (pin "3") (pinfunction "VISNS_3") (pintype "passive"))
    )
    (net (code "36") (name "VIN") (class "Default")
      (node (ref "C54") (pin "1") (pinfunction "1_1") (pintype "passive"))
      (node (ref "C55") (pin "1") (pinfunction "1_1") (pintype "passive"))
      (node (ref "C56") (pin "1") (pinfunction "1_1") (pintype "passive"))
      (node (ref "C57") (pin "1") (pinfunction "1_1") (pintype "passive"))
      (node (ref "D4") (pin "2") (pinfunction "A_2") (pintype "passive"))
      (node (ref "J4") (pin "1") (pinfunction "1_1") (pintype "passive"))
      (node (ref "Q1") (pin "1") (pinfunction "DRAIN_1") (pintype "passive"))
      (node (ref "Q1") (pin "2") (pinfunction "DRAIN_2") (pintype "passive"))
      (node (ref "Q1") (pin "5") (pinfunction "DRAIN_5") (pintype "passive"))
      (node (ref "Q1") (pin "6") (pinfunction "DRAIN_6") (pintype "passive"))
      (node (ref "Q1") (pin "8") (pinfunction "DRAIN_8") (pintype "passive"))
      (node (ref "R29") (pin "2") (pinfunction "2_2") (pintype "passive"))
      (node (ref "R31") (pin "2") (pinfunction "2_2") (pintype "passive"))
    )
    (net (code "37") (name "unconnected-(J3-Pad4)") (class "Default")
      (node (ref "J3") (pin "4") (pinfunction "4_4") (pintype "passive+no_connect"))
    )
    (net (code "38") (name "unconnected-(J3-Pad5)") (class "Default")
      (node (ref "J3") (pin "5") (pinfunction "5_5") (pintype "passive+no_connect"))
    )
    (net (code "39") (name "unconnected-(J3-Pad7)") (class "Default")
      (node (ref "J3") (pin "7") (pinfunction "7_7") (pintype "passive+no_connect"))
    )
    (net (code "40") (name "unconnected-(J3-Pad8)") (class "Default")
      (node (ref "J3") (pin "8") (pinfunction "8_8") (pintype "passive+no_connect"))
    )
  )
)
